# N_Shift.net
KiCad netlist of a schematic drawn in Altium Designer
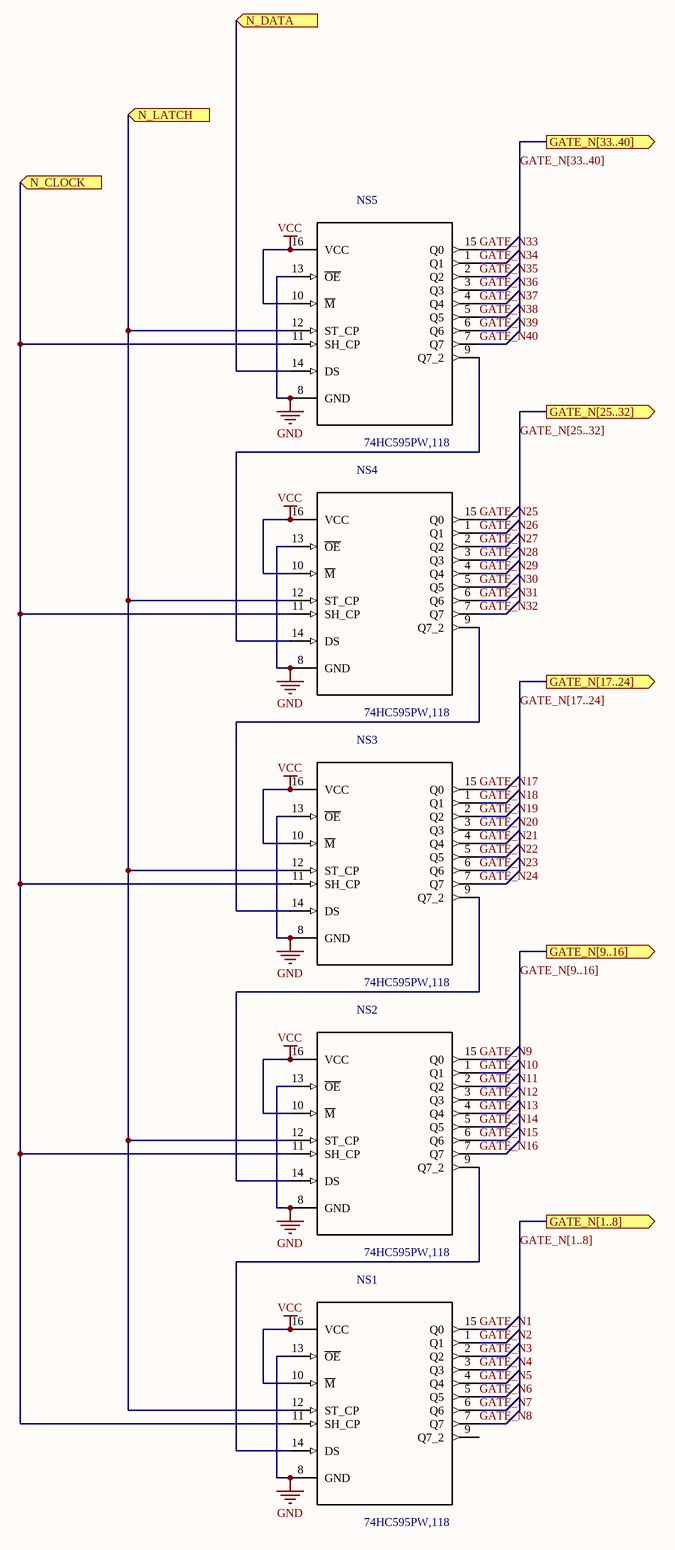
[diagram p0: N_Shift.SchDoc]

(export (version "E")
  (design (tool "Eeschema 10.0.6"))
  (components
    (comp (ref "NS1")
      (value "74HC595PW,118")
      (footprint "SOP65P640X110-16N")
      (description "8-bit serial-in%2C serial or parallel-out shift register with output latches%3B 3-state")
      (fields (field (name "MF") "NXP Semiconductors"))
      (libsource (lib "74HC595PW_118") (part "74HC595PW,118"))
    )
    (comp (ref "NS2")
      (value "74HC595PW,118")
      (footprint "SOP65P640X110-16N")
      (description "8-bit serial-in%2C serial or parallel-out shift register with output latches%3B 3-state")
      (fields (field (name "MF") "NXP Semiconductors"))
      (libsource (lib "74HC595PW_118") (part "74HC595PW,118"))
    )
    (comp (ref "NS3")
      (value "74HC595PW,118")
      (footprint "SOP65P640X110-16N")
      (description "8-bit serial-in%2C serial or parallel-out shift register with output latches%3B 3-state")
      (fields (field (name "MF") "NXP Semiconductors"))
      (libsource (lib "74HC595PW_118") (part "74HC595PW,118"))
    )
    (comp (ref "NS4")
      (value "74HC595PW,118")
      (footprint "SOP65P640X110-16N")
      (description "8-bit serial-in%2C serial or parallel-out shift register with output latches%3B 3-state")
      (fields (field (name "MF") "NXP Semiconductors"))
      (libsource (lib "74HC595PW_118") (part "74HC595PW,118"))
    )
    (comp (ref "NS5")
      (value "74HC595PW,118")
      (footprint "SOP65P640X110-16N")
      (description "8-bit serial-in%2C serial or parallel-out shift register with output latches%3B 3-state")
      (fields (field (name "MF") "NXP Semiconductors"))
      (libsource (lib "74HC595PW_118") (part "74HC595PW,118"))
    )
  )
  (nets
    (net (code "1") (name "/GATE_N1") (class "Default")
      (node (ref "NS1") (pin "15") (pinfunction "Q0_15") (pintype "output"))
    )
    (net (code "2") (name "/GATE_N2") (class "Default")
      (node (ref "NS1") (pin "1") (pinfunction "Q1_1") (pintype "output"))
    )
    (net (code "3") (name "/GATE_N3") (class "Default")
      (node (ref "NS1") (pin "2") (pinfunction "Q2_2") (pintype "output"))
    )
    (net (code "4") (name "/GATE_N4") (class "Default")
      (node (ref "NS1") (pin "3") (pinfunction "Q3_3") (pintype "output"))
    )
    (net (code "5") (name "/GATE_N5") (class "Default")
      (node (ref "NS1") (pin "4") (pinfunction "Q4_4") (pintype "output"))
    )
    (net (code "6") (name "/GATE_N6") (class "Default")
      (node (ref "NS1") (pin "5") (pinfunction "Q5_5") (pintype "output"))
    )
    (net (code "7") (name "/GATE_N7") (class "Default")
      (node (ref "NS1") (pin "6") (pinfunction "Q6_6") (pintype "output"))
    )
    (net (code "8") (name "/GATE_N8") (class "Default")
      (node (ref "NS1") (pin "7") (pinfunction "Q7_7") (pintype "output"))
    )
    (net (code "9") (name "/GATE_N9") (class "Default")
      (node (ref "NS2") (pin "15") (pinfunction "Q0_15") (pintype "output"))
    )
    (net (code "10") (name "/GATE_N10") (class "Default")
      (node (ref "NS2") (pin "1") (pinfunction "Q1_1") (pintype "output"))
    )
    (net (code "11") (name "/GATE_N11") (class "Default")
      (node (ref "NS2") (pin "2") (pinfunction "Q2_2") (pintype "output"))
    )
    (net (code "12") (name "/GATE_N12") (class "Default")
      (node (ref "NS2") (pin "3") (pinfunction "Q3_3") (pintype "output"))
    )
    (net (code "13") (name "/GATE_N13") (class "Default")
      (node (ref "NS2") (pin "4") (pinfunction "Q4_4") (pintype "output"))
    )
    (net (code "14") (name "/GATE_N14") (class "Default")
      (node (ref "NS2") (pin "5") (pinfunction "Q5_5") (pintype "output"))
    )
    (net (code "15") (name "/GATE_N15") (class "Default")
      (node (ref "NS2") (pin "6") (pinfunction "Q6_6") (pintype "output"))
    )
    (net (code "16") (name "/GATE_N16") (class "Default")
      (node (ref "NS2") (pin "7") (pinfunction "Q7_7") (pintype "output"))
    )
    (net (code "17") (name "/GATE_N17") (class "Default")
      (node (ref "NS3") (pin "15") (pinfunction "Q0_15") (pintype "output"))
    )
    (net (code "18") (name "/GATE_N18") (class "Default")
      (node (ref "NS3") (pin "1") (pinfunction "Q1_1") (pintype "output"))
    )
    (net (code "19") (name "/GATE_N19") (class "Default")
      (node (ref "NS3") (pin "2") (pinfunction "Q2_2") (pintype "output"))
    )
    (net (code "20") (name "/GATE_N20") (class "Default")
      (node (ref "NS3") (pin "3") (pinfunction "Q3_3") (pintype "output"))
    )
    (net (code "21") (name "/GATE_N21") (class "Default")
      (node (ref "NS3") (pin "4") (pinfunction "Q4_4") (pintype "output"))
    )
    (net (code "22") (name "/GATE_N22") (class "Default")
      (node (ref "NS3") (pin "5") (pinfunction "Q5_5") (pintype "output"))
    )
    (net (code "23") (name "/GATE_N23") (class "Default")
      (node (ref "NS3") (pin "6") (pinfunction "Q6_6") (pintype "output"))
    )
    (net (code "24") (name "/GATE_N24") (class "Default")
      (node (ref "NS3") (pin "7") (pinfunction "Q7_7") (pintype "output"))
    )
    (net (code "25") (name "/GATE_N25") (class "Default")
      (node (ref "NS4") (pin "15") (pinfunction "Q0_15") (pintype "output"))
    )
    (net (code "26") (name "/GATE_N26") (class "Default")
      (node (ref "NS4") (pin "1") (pinfunction "Q1_1") (pintype "output"))
    )
    (net (code "27") (name "/GATE_N27") (class "Default")
      (node (ref "NS4") (pin "2") (pinfunction "Q2_2") (pintype "output"))
    )
    (net (code "28") (name "/GATE_N28") (class "Default")
      (node (ref "NS4") (pin "3") (pinfunction "Q3_3") (pintype "output"))
    )
    (net (code "29") (name "/GATE_N29") (class "Default")
      (node (ref "NS4") (pin "4") (pinfunction "Q4_4") (pintype "output"))
    )
    (net (code "30") (name "/GATE_N30") (class "Default")
      (node (ref "NS4") (pin "5") (pinfunction "Q5_5") (pintype "output"))
    )
    (net (code "31") (name "/GATE_N31") (class "Default")
      (node (ref "NS4") (pin "6") (pinfunction "Q6_6") (pintype "output"))
    )
    (net (code "32") (name "/GATE_N32") (class "Default")
      (node (ref "NS4") (pin "7") (pinfunction "Q7_7") (pintype "output"))
    )
    (net (code "33") (name "/GATE_N33") (class "Default")
      (node (ref "NS5") (pin "15") (pinfunction "Q0_15") (pintype "output"))
    )
    (net (code "34") (name "/GATE_N34") (class "Default")
      (node (ref "NS5") (pin "1") (pinfunction "Q1_1") (pintype "output"))
    )
    (net (code "35") (name "/GATE_N35") (class "Default")
      (node (ref "NS5") (pin "2") (pinfunction "Q2_2") (pintype "output"))
    )
    (net (code "36") (name "/GATE_N36") (class "Default")
      (node (ref "NS5") (pin "3") (pinfunction "Q3_3") (pintype "output"))
    )
    (net (code "37") (name "/GATE_N37") (class "Default")
      (node (ref "NS5") (pin "4") (pinfunction "Q4_4") (pintype "output"))
    )
    (net (code "38") (name "/GATE_N38") (class "Default")
      (node (ref "NS5") (pin "5") (pinfunction "Q5_5") (pintype "output"))
    )
    (net (code "39") (name "/GATE_N39") (class "Default")
      (node (ref "NS5") (pin "6") (pinfunction "Q6_6") (pintype "output"))
    )
    (net (code "40") (name "/GATE_N40") (class "Default")
      (node (ref "NS5") (pin "7") (pinfunction "Q7_7") (pintype "output"))
    )
    (net (code "46") (name "/N_CLOCK") (class "Default")
      (node (ref "NS1") (pin "11") (pinfunction "SH_CP_11") (pintype "input"))
      (node (ref "NS2") (pin "11") (pinfunction "SH_CP_11") (pintype "input"))
      (node (ref "NS3") (pin "11") (pinfunction "SH_CP_11") (pintype "input"))
      (node (ref "NS4") (pin "11") (pinfunction "SH_CP_11") (pintype "input"))
      (node (ref "NS5") (pin "11") (pinfunction "SH_CP_11") (pintype "input"))
    )
    (net (code "47") (name "/N_DATA") (class "Default")
      (node (ref "NS5") (pin "14") (pinfunction "DS_14") (pintype "input"))
    )
    (net (code "48") (name "/N_LATCH") (class "Default")
      (node (ref "NS1") (pin "12") (pinfunction "ST_CP_12") (pintype "input"))
      (node (ref "NS2") (pin "12") (pinfunction "ST_CP_12") (pintype "input"))
      (node (ref "NS3") (pin "12") (pinfunction "ST_CP_12") (pintype "input"))
      (node (ref "NS4") (pin "12") (pinfunction "ST_CP_12") (pintype "input"))
      (node (ref "NS5") (pin "12") (pinfunction "ST_CP_12") (pintype "input"))
    )
    (net (code "49") (name "GND") (class "Default")
      (node (ref "NS1") (pin "13") (pinfunction "~{OE}_13") (pintype "input"))
      (node (ref "NS1") (pin "8") (pinfunction "GND_8") (pintype "passive"))
      (node (ref "NS2") (pin "13") (pinfunction "~{OE}_13") (pintype "input"))
      (node (ref "NS2") (pin "8") (pinfunction "GND_8") (pintype "passive"))
      (node (ref "NS3") (pin "13") (pinfunction "~{OE}_13") (pintype "input"))
      (node (ref "NS3") (pin "8") (pinfunction "GND_8") (pintype "passive"))
      (node (ref "NS4") (pin "13") (pinfunction "~{OE}_13") (pintype "input"))
      (node (ref "NS4") (pin "8") (pinfunction "GND_8") (pintype "passive"))
      (node (ref "NS5") (pin "13") (pinfunction "~{OE}_13") (pintype "input"))
      (node (ref "NS5") (pin "8") (pinfunction "GND_8") (pintype "passive"))
    )
    (net (code "50") (name "Net-(NS1-DS)") (class "Default")
      (node (ref "NS1") (pin "14") (pinfunction "DS_14") (pintype "input"))
      (node (ref "NS2") (pin "9") (pinfunction "Q7_2_9") (pintype "output"))
    )
    (net (code "51") (name "Net-(NS2-DS)") (class "Default")
      (node (ref "NS2") (pin "14") (pinfunction "DS_14") (pintype "input"))
      (node (ref "NS3") (pin "9") (pinfunction "Q7_2_9") (pintype "output"))
    )
    (net (code "52") (name "Net-(NS3-DS)") (class "Default")
      (node (ref "NS3") (pin "14") (pinfunction "DS_14") (pintype "input"))
      (node (ref "NS4") (pin "9") (pinfunction "Q7_2_9") (pintype "output"))
    )
    (net (code "53") (name "Net-(NS4-DS)") (class "Default")
      (node (ref "NS4") (pin "14") (pinfunction "DS_14") (pintype "input"))
      (node (ref "NS5") (pin "9") (pinfunction "Q7_2_9") (pintype "output"))
    )
    (net (code "54") (name "VCC") (class "Default")
      (node (ref "NS1") (pin "10") (pinfunction "M~{\r}_10") (pintype "input"))
      (node (ref "NS1") (pin "16") (pinfunction "VCC_16") (pintype "power_in"))
      (node (ref "NS2") (pin "10") (pinfunction "M~{\r}_10") (pintype "input"))
      (node (ref "NS2") (pin "16") (pinfunction "VCC_16") (pintype "power_in"))
      (node (ref "NS3") (pin "10") (pinfunction "M~{\r}_10") (pintype "input"))
      (node (ref "NS3") (pin "16") (pinfunction "VCC_16") (pintype "power_in"))
      (node (ref "NS4") (pin "10") (pinfunction "M~{\r}_10") (pintype "input"))
      (node (ref "NS4") (pin "16") (pinfunction "VCC_16") (pintype "power_in"))
      (node (ref "NS5") (pin "10") (pinfunction "M~{\r}_10") (pintype "input"))
      (node (ref "NS5") (pin "16") (pinfunction "VCC_16") (pintype "power_in"))
    )
    (net (code "55") (name "unconnected-(NS1-Q7_2-Pad9)") (class "Default")
      (node (ref "NS1") (pin "9") (pinfunction "Q7_2_9") (pintype "output"))
    )
  )
)
